# Copy_of_ST_LINK_V3E.net
KiCad netlist of a schematic drawn in Altium Designer
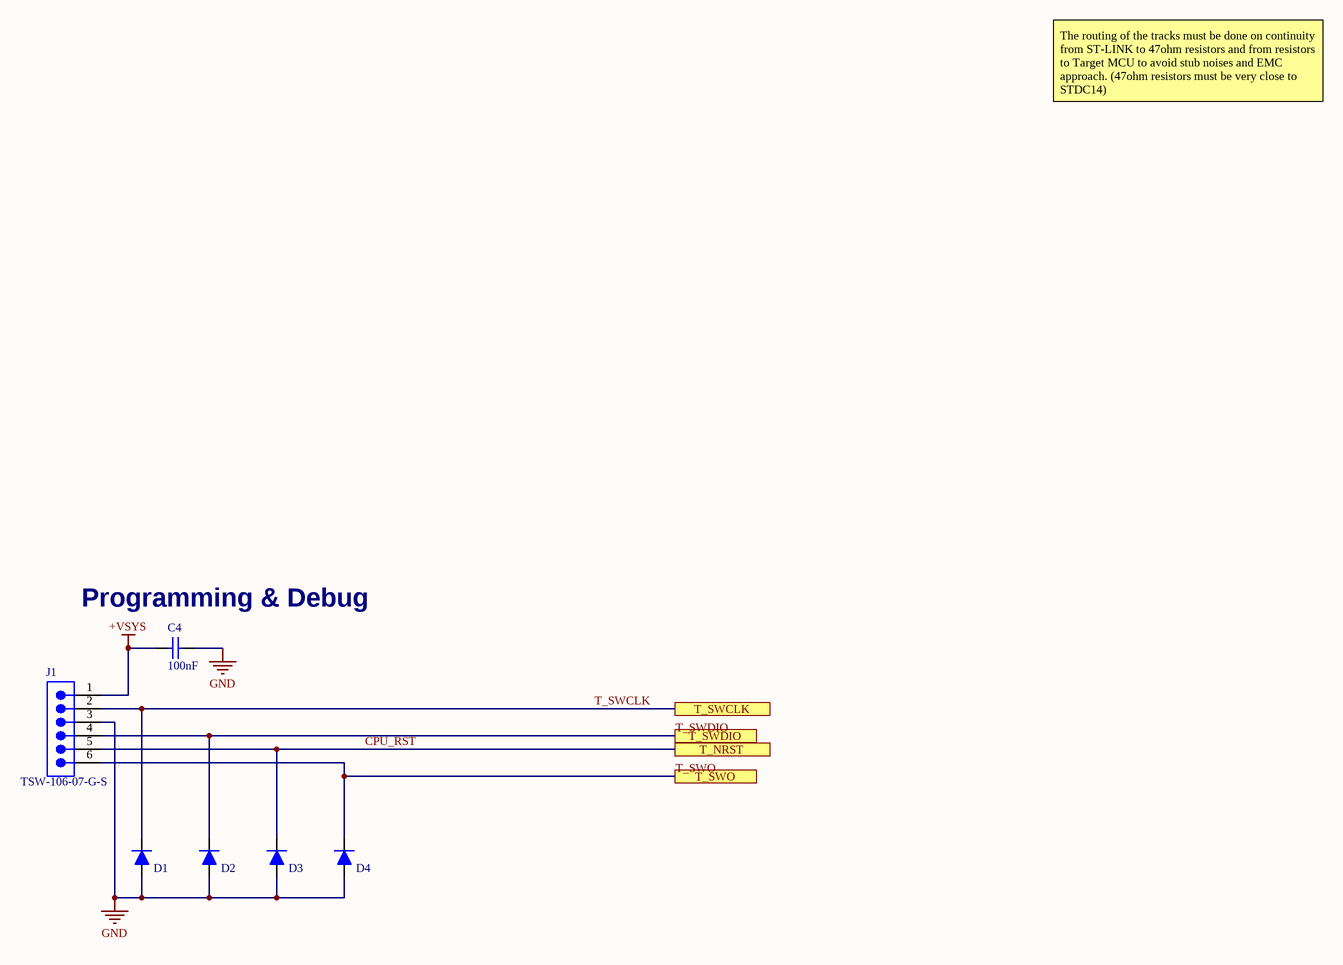
[diagram p0: Copy of ST_LINK_V3E.SchDoc]

(export (version "E")
  (design (tool "Eeschema 10.0.6"))
  (components
    (comp (ref "C4")
      (value "100nF")
      (footprint "0402")
      (description "0402 (1005Metric) CERAMIC CAPACITOR ceramic capacitor 50V 0.1muF ±10% X5R")
      (fields
        (field (name "MANUFACTURER") "Kyocera AVX")
        (field (name "MANUFACTURER PART NUMBER") "04025D104KAT2A")
      )
      (libsource (lib "Board") (part "04025D104KAT2A"))
    )
    (comp (ref "D1")
      (value "CG0603MLC-3.3LE")
      (footprint "ESD PROTECTOR")
      (description "MLC Series Multilayer Varistor 0.5pF; Clamping 25V 0603 Case")
      (fields (field (name "MANUFACTURER") "Bourns") (field (name "VOLTAGE") "3.3V"))
      (libsource (lib "PCI-MON_MAQ_ROT_IOT_A") (part "CG0603MLC-3.3LE"))
    )
    (comp (ref "D2")
      (value "CG0603MLC-3.3LE")
      (footprint "ESD PROTECTOR")
      (description "MLC Series Multilayer Varistor 0.5pF; Clamping 25V 0603 Case")
      (fields (field (name "MANUFACTURER") "Bourns") (field (name "VOLTAGE") "3.3V"))
      (libsource (lib "PCI-MON_MAQ_ROT_IOT_A") (part "CG0603MLC-3.3LE"))
    )
    (comp (ref "D3")
      (value "CG0603MLC-3.3LE")
      (footprint "ESD PROTECTOR")
      (description "MLC Series Multilayer Varistor 0.5pF; Clamping 25V 0603 Case")
      (fields (field (name "MANUFACTURER") "Bourns") (field (name "VOLTAGE") "3.3V"))
      (libsource (lib "PCI-MON_MAQ_ROT_IOT_A") (part "CG0603MLC-3.3LE"))
    )
    (comp (ref "D4")
      (value "CG0603MLC-3.3LE")
      (footprint "ESD PROTECTOR")
      (description "MLC Series Multilayer Varistor 0.5pF; Clamping 25V 0603 Case")
      (fields (field (name "MANUFACTURER") "Bourns") (field (name "VOLTAGE") "3.3V"))
      (libsource (lib "PCI-MON_MAQ_ROT_IOT_A") (part "CG0603MLC-3.3LE"))
    )
    (comp (ref "J1")
      (value "TSW-106-07-G-S")
      (footprint "SMTC-TSW-106-07-X-S")
      (description "0.025\" SQ Post Header, Through-hole, Vertical, -55 to 125 degC, 2.54 mm Pitch, 6-Pin, Male, RoHS")
      (fields (field (name "MANUFACTURER") "Samtec"))
      (libsource (lib "Altium Content Vault") (part "SMTC-TSW-106-X-X-S-X"))
    )
  )
  (nets
    (net (code "1") (name "+VSYS") (class "Default")
      (node (ref "C4") (pin "1") (pinfunction "1_1") (pintype "passive"))
      (node (ref "J1") (pin "1") (pinfunction "1_1") (pintype "passive"))
    )
    (net (code "3") (name "/CPU_RST") (class "Default")
      (node (ref "D3") (pin "1") (pinfunction "K_1") (pintype "passive"))
      (node (ref "J1") (pin "5") (pinfunction "5_5") (pintype "passive"))
    )
    (net (code "4") (name "/T_SWCLK") (class "Default")
      (node (ref "D1") (pin "1") (pinfunction "K_1") (pintype "passive"))
      (node (ref "J1") (pin "2") (pinfunction "2_2") (pintype "passive"))
    )
    (net (code "5") (name "/T_SWDIO") (class "Default")
      (node (ref "D2") (pin "1") (pinfunction "K_1") (pintype "passive"))
      (node (ref "J1") (pin "4") (pinfunction "4_4") (pintype "passive"))
    )
    (net (code "6") (name "/T_SWO") (class "Default")
      (node (ref "D4") (pin "1") (pinfunction "K_1") (pintype "passive"))
      (node (ref "J1") (pin "6") (pinfunction "6_6") (pintype "passive"))
    )
    (net (code "7") (name "GND") (class "Default")
      (node (ref "C4") (pin "2") (pinfunction "2_2") (pintype "passive"))
      (node (ref "D1") (pin "2") (pinfunction "A_2") (pintype "passive"))
      (node (ref "D2") (pin "2") (pinfunction "A_2") (pintype "passive"))
      (node (ref "D3") (pin "2") (pinfunction "A_2") (pintype "passive"))
      (node (ref "D4") (pin "2") (pinfunction "A_2") (pintype "passive"))
      (node (ref "J1") (pin "3") (pinfunction "3_3") (pintype "passive"))
    )
  )
)
